# EMPEL_BkBstPCB.net
KiCad netlist of a schematic drawn in EasyEDA Pro
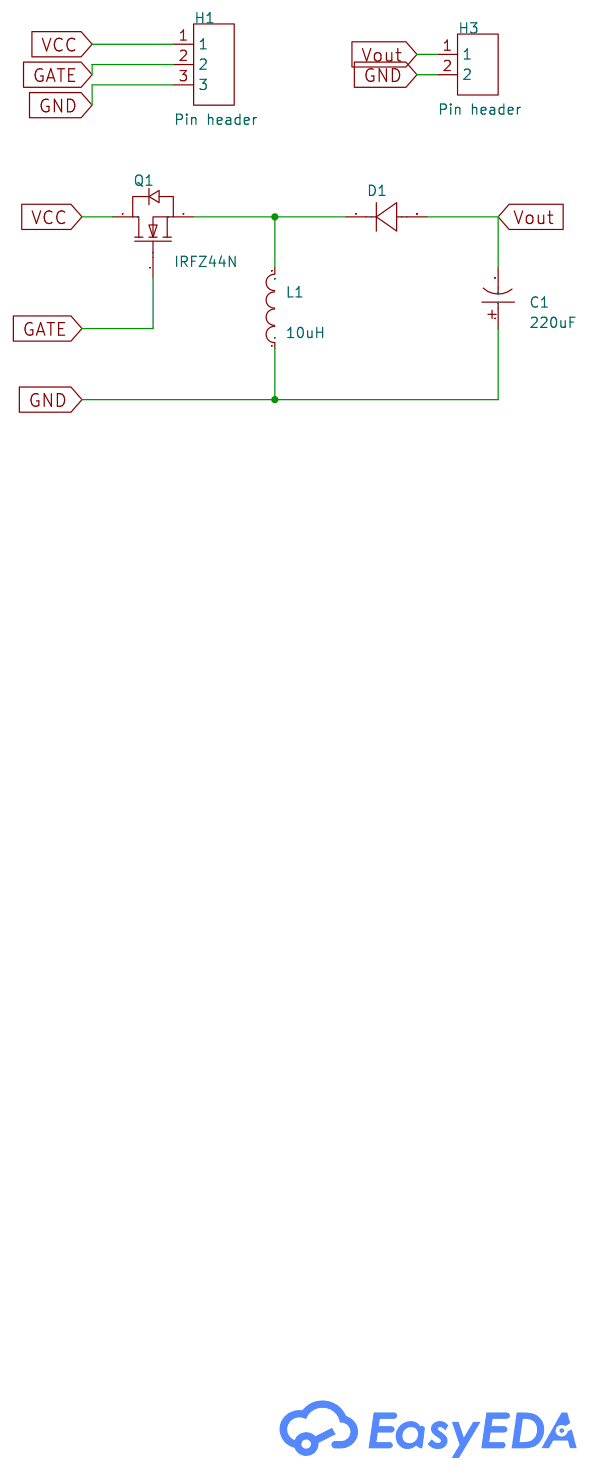
[diagram p0: schematic sheet]

(export (version "E")
  (design (tool "Eeschema 10.0.6"))
  (components
    (comp (ref "C1")
      (value "220uF")
      (footprint "easyedapro:CAP-TH_BD10.0-P5.00-D1.0-FD")
      (fields
        (field (name "Manufacturer Part") "50PX220MEFC10X12.5")
        (field (name "Manufacturer") "Rubycon(红宝石)")
      )
      (libsource (lib "easyedapro") (part "50PX220MEFC10X12.5"))
    )
    (comp (ref "D1")
      (value "~")
      (footprint "easyedapro:SMA_L4.4-W2.8-LS5.4-RD")
      (libsource (lib "easyedapro") (part "D_1N4007"))
    )
    (comp (ref "H1")
      (value "Pin header")
      (footprint "easyedapro:HDR-TH_3P-P2.54-V-M-1")
      (fields (field (name "Manufacturer") "hanxia(韩下)"))
      (libsource (lib "easyedapro") (part "HX PH254-01-03-Z-L11.5 PCB PIN HEADER"))
    )
    (comp (ref "H3")
      (value "Pin header")
      (footprint "easyedapro:HDR-TH_2P-P2.54-V-M")
      (fields (field (name "Manufacturer") "hanxia(韩下)"))
      (libsource (lib "easyedapro") (part "HX PH254-01-02-Z-L11.5 MALE HEADER CONNECTOR"))
    )
    (comp (ref "L1") (value "10uH") (footprint "easyedapro:L0603") (libsource (lib "easyedapro") (part "电感")))
    (comp (ref "Q1")
      (value "IRFZ44N")
      (footprint "easyedapro:TO-220-3_L9.9-W4.5-P2.54-L")
      (fields (field (name "Manufacturer") "minos(迈诺斯)"))
      (libsource (lib "easyedapro") (part "IRFZ44N"))
    )
  )
  (nets
    (net (code "1") (name "GATE") (class "Default")
      (node (ref "H1") (pin "2") (pinfunction "2_2") (pintype "unspecified"))
      (node (ref "Q1") (pin "1") (pinfunction "G_1") (pintype "unspecified"))
    )
    (net (code "2") (name "GND") (class "Default")
      (node (ref "C1") (pin "1") (pinfunction "1_1") (pintype "input"))
      (node (ref "H1") (pin "3") (pinfunction "3_3") (pintype "unspecified"))
      (node (ref "H3") (pin "2") (pinfunction "2_2") (pintype "unspecified"))
      (node (ref "L1") (pin "1") (pinfunction "1_1") (pintype "input"))
    )
    (net (code "3") (name "Net-(D1-K)") (class "Default")
      (node (ref "D1") (pin "1") (pinfunction "K_1") (pintype "input"))
      (node (ref "L1") (pin "2") (pinfunction "2_2") (pintype "input"))
      (node (ref "Q1") (pin "3") (pinfunction "S_3") (pintype "unspecified"))
    )
    (net (code "4") (name "VCC") (class "Default")
      (node (ref "H1") (pin "1") (pinfunction "1_1") (pintype "unspecified"))
      (node (ref "Q1") (pin "2") (pinfunction "D_2") (pintype "unspecified"))
    )
    (net (code "5") (name "Vout") (class "Default")
      (node (ref "C1") (pin "2") (pinfunction "2_2") (pintype "input"))
      (node (ref "D1") (pin "2") (pinfunction "A_2") (pintype "input"))
      (node (ref "H3") (pin "1") (pinfunction "1_1") (pintype "unspecified"))
    )
  )
)
